# LCD.net
KiCad netlist of a schematic drawn in Altium Designer
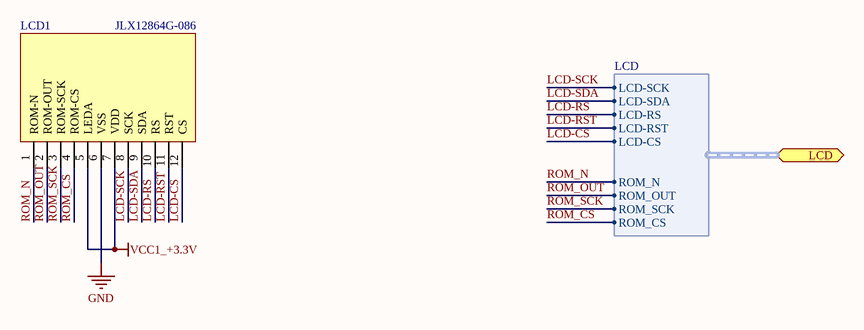
[diagram p0: LCD.SchDoc]

(export (version "E")
  (design (tool "Eeschema 10.0.6"))
  (components
    (comp (ref "LCD1")
      (value "JLX12864G-086")
      (footprint "12864-IIC")
      (description "LCD")
      (libsource (lib "FR5969v1.0") (part "JLX12864G-086"))
    )
  )
  (nets
    (net (code "2") (name "/LCD-CS") (class "Default")
      (node (ref "LCD1") (pin "12") (pinfunction "CS_12") (pintype "passive"))
    )
    (net (code "3") (name "/LCD-RS") (class "Default")
      (node (ref "LCD1") (pin "10") (pinfunction "RS_10") (pintype "passive"))
    )
    (net (code "4") (name "/LCD-RST") (class "Default")
      (node (ref "LCD1") (pin "11") (pinfunction "RST_11") (pintype "passive"))
    )
    (net (code "5") (name "/LCD-SCK") (class "Default")
      (node (ref "LCD1") (pin "8") (pinfunction "SCK_8") (pintype "passive"))
    )
    (net (code "6") (name "/LCD-SDA") (class "Default")
      (node (ref "LCD1") (pin "9") (pinfunction "SDA_9") (pintype "passive"))
    )
    (net (code "7") (name "/ROM_CS") (class "Default")
      (node (ref "LCD1") (pin "4") (pinfunction "ROM-CS_4") (pintype "passive"))
    )
    (net (code "8") (name "/ROM_N") (class "Default")
      (node (ref "LCD1") (pin "1") (pinfunction "ROM-N_1") (pintype "passive"))
    )
    (net (code "9") (name "/ROM_OUT") (class "Default")
      (node (ref "LCD1") (pin "2") (pinfunction "ROM-OUT_2") (pintype "passive"))
    )
    (net (code "10") (name "/ROM_SCK") (class "Default")
      (node (ref "LCD1") (pin "3") (pinfunction "ROM-SCK_3") (pintype "passive"))
    )
    (net (code "12") (name "GND") (class "Default")
      (node (ref "LCD1") (pin "6") (pinfunction "VSS_6") (pintype "passive"))
    )
    (net (code "13") (name "VCC1_+3.3V") (class "Default")
      (node (ref "LCD1") (pin "5") (pinfunction "LEDA_5") (pintype "passive"))
      (node (ref "LCD1") (pin "7") (pinfunction "VDD_7") (pintype "passive"))
    )
  )
)
